# blackmagic_richardeoin.net
KiCad netlist of a schematic drawn in EAGLE
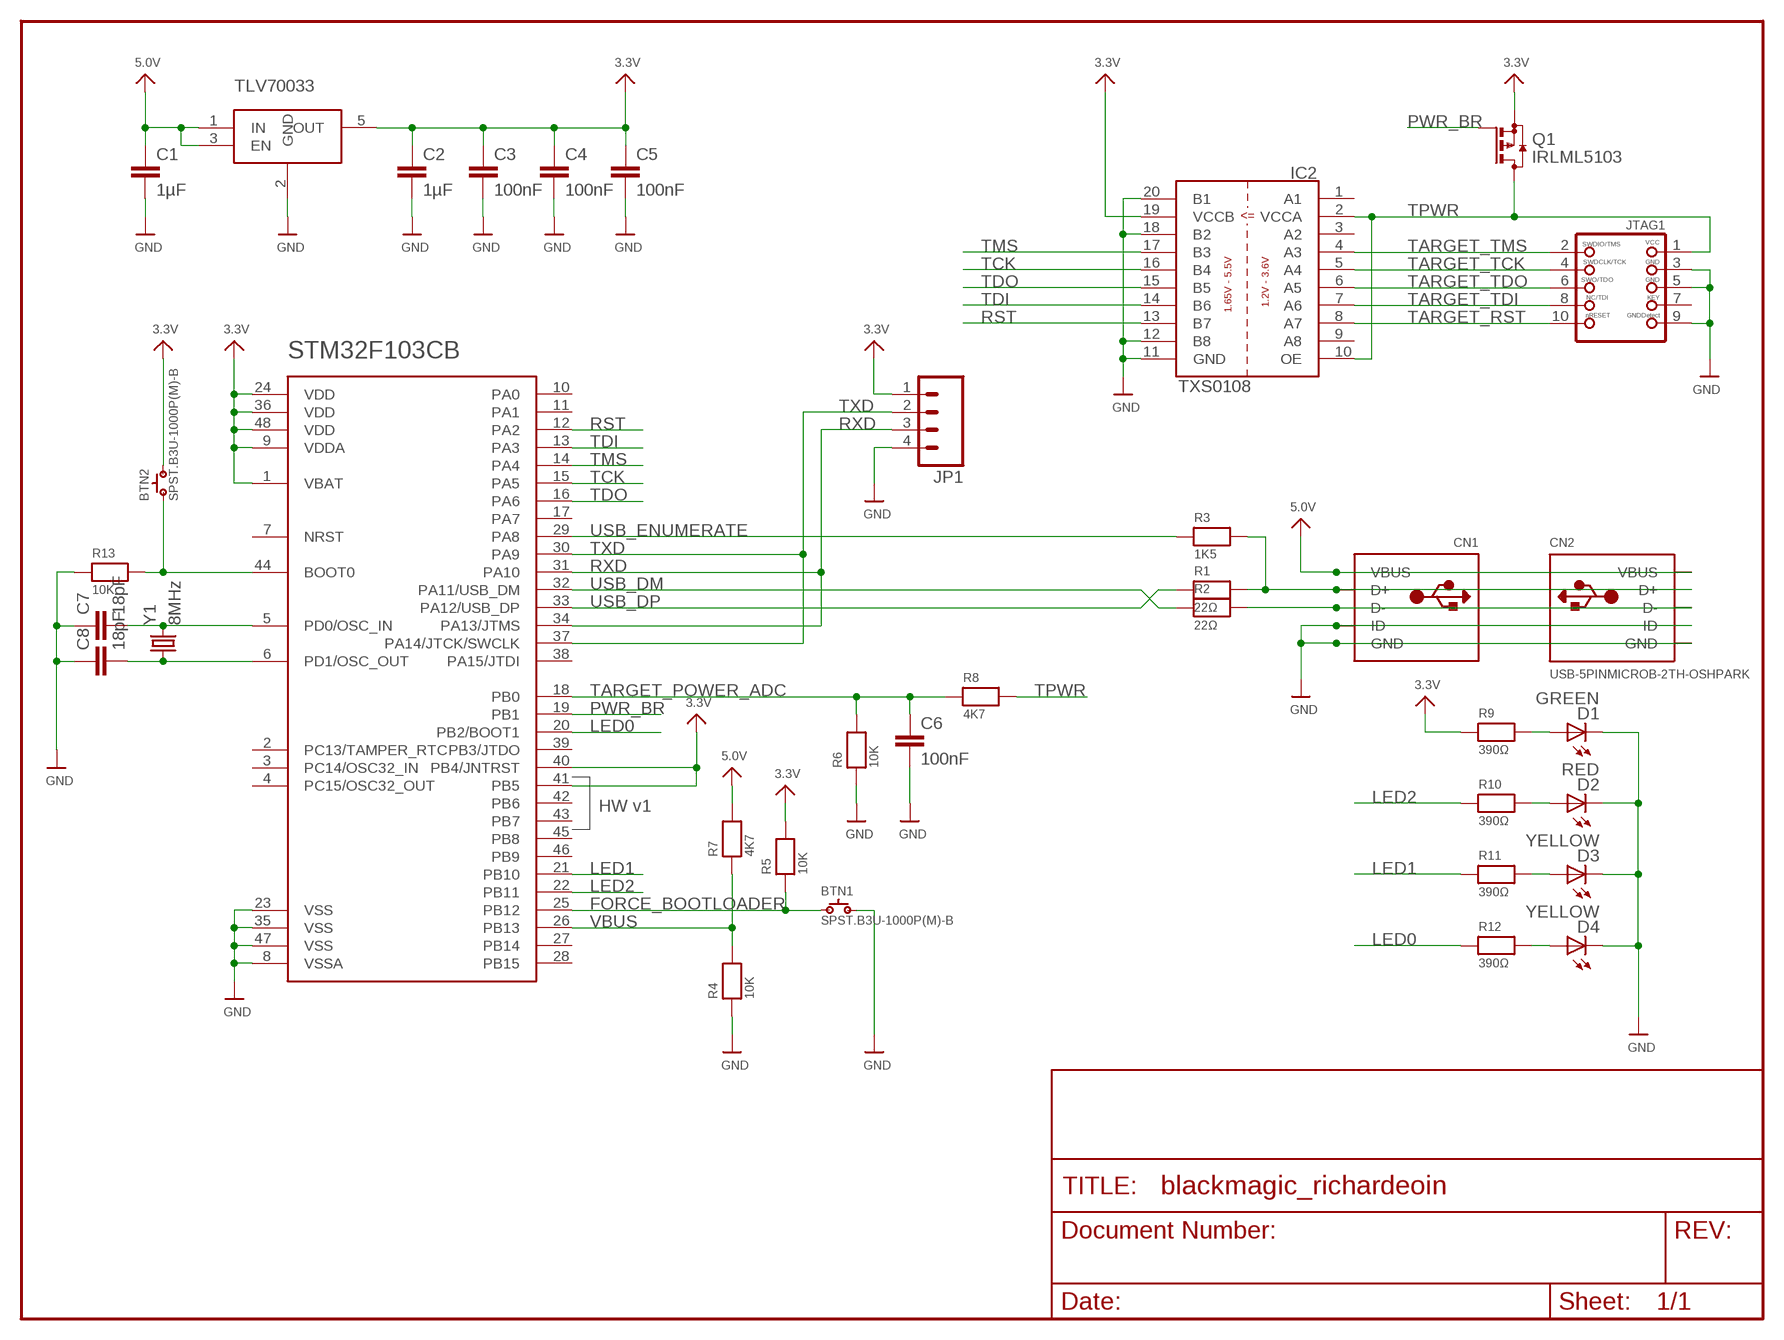
[diagram p0: schematic, sheet 1]

(export (version "E")
  (design (tool "Eeschema 10.0.6"))
  (components
    (comp (ref "BTN1")
      (value "SPST.B3U-1000P(M)-B")
      (footprint "eagle-import:B3U-1000P(M)-B")
      (libsource (lib "eagle-import") (part "SPST.B3U-1000P(M)-B"))
    )
    (comp (ref "BTN2")
      (value "SPST.B3U-1000P(M)-B")
      (footprint "eagle-import:B3U-1000P(M)-B")
      (libsource (lib "eagle-import") (part "SPST.B3U-1000P(M)-B"))
    )
    (comp (ref "C1")
      (value "1µF")
      (footprint "eagle-import:C0603K")
      (libsource (lib "eagle-import") (part "C-EUC0603K"))
    )
    (comp (ref "C2")
      (value "1µF")
      (footprint "eagle-import:C0603K")
      (libsource (lib "eagle-import") (part "C-EUC0603K"))
    )
    (comp (ref "C3")
      (value "100nF")
      (footprint "eagle-import:C0603K")
      (libsource (lib "eagle-import") (part "C-EUC0603K"))
    )
    (comp (ref "C4")
      (value "100nF")
      (footprint "eagle-import:C0603K")
      (libsource (lib "eagle-import") (part "C-EUC0603K"))
    )
    (comp (ref "C5")
      (value "100nF")
      (footprint "eagle-import:C0603K")
      (libsource (lib "eagle-import") (part "C-EUC0603K"))
    )
    (comp (ref "C6")
      (value "100nF")
      (footprint "eagle-import:C0603K")
      (libsource (lib "eagle-import") (part "C-EUC0603K"))
    )
    (comp (ref "C7")
      (value "18pF")
      (footprint "eagle-import:C0603K")
      (libsource (lib "eagle-import") (part "C-EUC0603K"))
    )
    (comp (ref "C8")
      (value "18pF")
      (footprint "eagle-import:C0603K")
      (libsource (lib "eagle-import") (part "C-EUC0603K"))
    )
    (comp (ref "CN1")
      (value "USBMINIB")
      (footprint "eagle-import:USB-MINIB")
      (libsource (lib "eagle-import") (part "USBMINIB"))
    )
    (comp (ref "CN2")
      (value "USB-5PINMICROB-2TH-OSHPARK")
      (footprint "eagle-import:USB-MICROB-2TH-OSHPARK")
      (libsource (lib "eagle-import") (part "USB-5PINMICROB-2TH-OSHPARK"))
    )
    (comp (ref "D1")
      (value "GREEN")
      (footprint "eagle-import:CHIPLED_0603")
      (libsource (lib "eagle-import") (part "LEDCHIPLED_0603"))
    )
    (comp (ref "D2")
      (value "RED")
      (footprint "eagle-import:CHIPLED_0603")
      (libsource (lib "eagle-import") (part "LEDCHIPLED_0603"))
    )
    (comp (ref "D3")
      (value "YELLOW")
      (footprint "eagle-import:CHIPLED_0603")
      (libsource (lib "eagle-import") (part "LEDCHIPLED_0603"))
    )
    (comp (ref "D4")
      (value "YELLOW")
      (footprint "eagle-import:CHIPLED_0603")
      (libsource (lib "eagle-import") (part "LEDCHIPLED_0603"))
    )
    (comp (ref "IC1")
      (value "STM32F_48PIN")
      (footprint "eagle-import:TQFP48")
      (libsource (lib "eagle-import") (part "STM32F_48PIN"))
    )
    (comp (ref "IC2")
      (value "TXS0108")
      (footprint "eagle-import:TSSOP20")
      (libsource (lib "eagle-import") (part "TX0108PWR"))
    )
    (comp (ref "IC3")
      (value "TLV70033DCK")
      (footprint "eagle-import:SC70-5L")
      (libsource (lib "eagle-import") (part "TLV700DCK"))
    )
    (comp (ref "JP1")
      (value "M04LOCK")
      (footprint "eagle-import:1X04_LOCK")
      (libsource (lib "eagle-import") (part "M04LOCK"))
    )
    (comp (ref "JTAG1")
      (value "JTAG-CORTEXM3TH")
      (footprint "eagle-import:2X05_1.27MM_TH")
      (libsource (lib "eagle-import") (part "JTAG-CORTEXM3TH"))
    )
    (comp (ref "Q1")
      (value "IRLML5103")
      (footprint "eagle-import:SOT23")
      (libsource (lib "eagle-import") (part "BSS84"))
    )
    (comp (ref "R1")
      (value "22Ω")
      (footprint "eagle-import:0603-MINI")
      (libsource (lib "eagle-import") (part "RESISTOR0603MINI"))
    )
    (comp (ref "R2")
      (value "22Ω")
      (footprint "eagle-import:0603-MINI")
      (libsource (lib "eagle-import") (part "RESISTOR0603MINI"))
    )
    (comp (ref "R3")
      (value "1K5")
      (footprint "eagle-import:0603-MINI")
      (libsource (lib "eagle-import") (part "RESISTOR0603MINI"))
    )
    (comp (ref "R4")
      (value "10K")
      (footprint "eagle-import:0603-MINI")
      (libsource (lib "eagle-import") (part "RESISTOR0603MINI"))
    )
    (comp (ref "R5")
      (value "10K")
      (footprint "eagle-import:0603-MINI")
      (libsource (lib "eagle-import") (part "RESISTOR0603MINI"))
    )
    (comp (ref "R6")
      (value "10K")
      (footprint "eagle-import:0603-MINI")
      (libsource (lib "eagle-import") (part "RESISTOR0603MINI"))
    )
    (comp (ref "R7")
      (value "4K7")
      (footprint "eagle-import:0603-MINI")
      (libsource (lib "eagle-import") (part "RESISTOR0603MINI"))
    )
    (comp (ref "R8")
      (value "4K7")
      (footprint "eagle-import:0603-MINI")
      (libsource (lib "eagle-import") (part "RESISTOR0603MINI"))
    )
    (comp (ref "R9")
      (value "390Ω")
      (footprint "eagle-import:0603-MINI")
      (libsource (lib "eagle-import") (part "RESISTOR0603MINI"))
    )
    (comp (ref "R10")
      (value "390Ω")
      (footprint "eagle-import:0603-MINI")
      (libsource (lib "eagle-import") (part "RESISTOR0603MINI"))
    )
    (comp (ref "R11")
      (value "390Ω")
      (footprint "eagle-import:0603-MINI")
      (libsource (lib "eagle-import") (part "RESISTOR0603MINI"))
    )
    (comp (ref "R12")
      (value "390Ω")
      (footprint "eagle-import:0603-MINI")
      (libsource (lib "eagle-import") (part "RESISTOR0603MINI"))
    )
    (comp (ref "R13")
      (value "10K")
      (footprint "eagle-import:0603-MINI")
      (libsource (lib "eagle-import") (part "RESISTOR0603MINI"))
    )
    (comp (ref "Y1")
      (value "8MHz")
      (footprint "eagle-import:CRYSTAL-SMD-5X3")
      (libsource (lib "eagle-import") (part "CRYSTAL5X3"))
    )
  )
  (nets
    (net (code "1") (name "/FORCE_BOOTLOADER") (class "Default")
      (node (ref "BTN1") (pin "1") (pinfunction "1_1") (pintype "bidirectional"))
      (node (ref "IC1") (pin "25") (pinfunction "PB12_25") (pintype "bidirectional"))
      (node (ref "R5") (pin "1") (pinfunction "1_1") (pintype "passive"))
    )
    (net (code "2") (name "/LED0") (class "Default")
      (node (ref "IC1") (pin "20") (pinfunction "PB2/BOOT1_20") (pintype "bidirectional"))
      (node (ref "R12") (pin "1") (pinfunction "1_1") (pintype "passive"))
    )
    (net (code "3") (name "/LED1") (class "Default")
      (node (ref "IC1") (pin "21") (pinfunction "PB10_21") (pintype "bidirectional"))
      (node (ref "R11") (pin "1") (pinfunction "1_1") (pintype "passive"))
    )
    (net (code "4") (name "/LED2") (class "Default")
      (node (ref "IC1") (pin "22") (pinfunction "PB11_22") (pintype "bidirectional"))
      (node (ref "R10") (pin "1") (pinfunction "1_1") (pintype "passive"))
    )
    (net (code "5") (name "/PWR_BR") (class "Default")
      (node (ref "IC1") (pin "19") (pinfunction "PB1_19") (pintype "bidirectional"))
      (node (ref "Q1") (pin "1") (pinfunction "G_1") (pintype "passive"))
    )
    (net (code "6") (name "/RST") (class "Default")
      (node (ref "IC1") (pin "12") (pinfunction "PA2_12") (pintype "bidirectional"))
      (node (ref "IC2") (pin "13") (pinfunction "B7_13") (pintype "bidirectional"))
    )
    (net (code "7") (name "/RXD") (class "Default")
      (node (ref "IC1") (pin "31") (pinfunction "PA10_31") (pintype "bidirectional"))
      (node (ref "IC1") (pin "34") (pinfunction "PA13/JTMS_34") (pintype "bidirectional"))
      (node (ref "JP1") (pin "3") (pinfunction "3_3") (pintype "passive"))
    )
    (net (code "8") (name "/TARGET_POWER_ADC") (class "Default")
      (node (ref "C6") (pin "1") (pinfunction "1_1") (pintype "passive"))
      (node (ref "IC1") (pin "18") (pinfunction "PB0_18") (pintype "bidirectional"))
      (node (ref "R6") (pin "2") (pinfunction "2_2") (pintype "passive"))
      (node (ref "R8") (pin "1") (pinfunction "1_1") (pintype "passive"))
    )
    (net (code "9") (name "/TARGET_RST") (class "Default")
      (node (ref "IC2") (pin "8") (pinfunction "A7_8") (pintype "bidirectional"))
      (node (ref "JTAG1") (pin "10") (pinfunction "10_10") (pintype "passive"))
    )
    (net (code "10") (name "/TARGET_TCK") (class "Default")
      (node (ref "IC2") (pin "5") (pinfunction "A4_5") (pintype "bidirectional"))
      (node (ref "JTAG1") (pin "4") (pinfunction "4_4") (pintype "passive"))
    )
    (net (code "11") (name "/TARGET_TDI") (class "Default")
      (node (ref "IC2") (pin "7") (pinfunction "A6_7") (pintype "bidirectional"))
      (node (ref "JTAG1") (pin "8") (pinfunction "8_8") (pintype "passive"))
    )
    (net (code "12") (name "/TARGET_TDO") (class "Default")
      (node (ref "IC2") (pin "6") (pinfunction "A5_6") (pintype "bidirectional"))
      (node (ref "JTAG1") (pin "6") (pinfunction "6_6") (pintype "passive"))
    )
    (net (code "13") (name "/TARGET_TMS") (class "Default")
      (node (ref "IC2") (pin "4") (pinfunction "A3_4") (pintype "bidirectional"))
      (node (ref "JTAG1") (pin "2") (pinfunction "2_2") (pintype "passive"))
    )
    (net (code "14") (name "/TCK") (class "Default")
      (node (ref "IC1") (pin "15") (pinfunction "PA5_15") (pintype "bidirectional"))
      (node (ref "IC2") (pin "16") (pinfunction "B4_16") (pintype "bidirectional"))
    )
    (net (code "15") (name "/TDI") (class "Default")
      (node (ref "IC1") (pin "13") (pinfunction "PA3_13") (pintype "bidirectional"))
      (node (ref "IC2") (pin "14") (pinfunction "B6_14") (pintype "bidirectional"))
    )
    (net (code "16") (name "/TDO") (class "Default")
      (node (ref "IC1") (pin "16") (pinfunction "PA6_16") (pintype "bidirectional"))
      (node (ref "IC2") (pin "15") (pinfunction "B5_15") (pintype "bidirectional"))
    )
    (net (code "17") (name "/TMS") (class "Default")
      (node (ref "IC1") (pin "14") (pinfunction "PA4_14") (pintype "bidirectional"))
      (node (ref "IC2") (pin "17") (pinfunction "B3_17") (pintype "bidirectional"))
    )
    (net (code "18") (name "/TPWR") (class "Default")
      (node (ref "IC2") (pin "10") (pinfunction "OE_10") (pintype "input"))
      (node (ref "IC2") (pin "2") (pinfunction "VCCA_2") (pintype "passive"))
      (node (ref "JTAG1") (pin "1") (pinfunction "1_1") (pintype "passive"))
      (node (ref "Q1") (pin "3") (pinfunction "D_3") (pintype "passive"))
      (node (ref "R8") (pin "2") (pinfunction "2_2") (pintype "passive"))
    )
    (net (code "19") (name "/TXD") (class "Default")
      (node (ref "IC1") (pin "30") (pinfunction "PA9_30") (pintype "bidirectional"))
      (node (ref "IC1") (pin "37") (pinfunction "PA14/JTCK/SWCLK_37") (pintype "bidirectional"))
      (node (ref "JP1") (pin "2") (pinfunction "2_2") (pintype "passive"))
    )
    (net (code "20") (name "/USB_DM") (class "Default")
      (node (ref "IC1") (pin "32") (pinfunction "PA11/USB_DM_32") (pintype "bidirectional"))
      (node (ref "R2") (pin "1") (pinfunction "1_1") (pintype "passive"))
    )
    (net (code "21") (name "/USB_DP") (class "Default")
      (node (ref "IC1") (pin "33") (pinfunction "PA12/USB_DP_33") (pintype "bidirectional"))
      (node (ref "R1") (pin "1") (pinfunction "1_1") (pintype "passive"))
    )
    (net (code "22") (name "/USB_ENUMERATE") (class "Default")
      (node (ref "IC1") (pin "29") (pinfunction "PA8_29") (pintype "bidirectional"))
      (node (ref "R3") (pin "1") (pinfunction "1_1") (pintype "passive"))
    )
    (net (code "23") (name "/VBUS") (class "Default")
      (node (ref "IC1") (pin "26") (pinfunction "PB13_26") (pintype "bidirectional"))
      (node (ref "R4") (pin "2") (pinfunction "2_2") (pintype "passive"))
      (node (ref "R7") (pin "1") (pinfunction "1_1") (pintype "passive"))
    )
    (net (code "24") (name "3.3V") (class "Default")
      (node (ref "BTN2") (pin "2") (pinfunction "2_2") (pintype "bidirectional"))
      (node (ref "C2") (pin "1") (pinfunction "1_1") (pintype "passive"))
      (node (ref "C3") (pin "1") (pinfunction "1_1") (pintype "passive"))
      (node (ref "C4") (pin "1") (pinfunction "1_1") (pintype "passive"))
      (node (ref "C5") (pin "1") (pinfunction "1_1") (pintype "passive"))
      (node (ref "IC1") (pin "1") (pinfunction "VBAT_1") (pintype "bidirectional"))
      (node (ref "IC1") (pin "24") (pinfunction "VDD_24") (pintype "bidirectional"))
      (node (ref "IC1") (pin "36") (pinfunction "VDD_36") (pintype "bidirectional"))
      (node (ref "IC1") (pin "40") (pinfunction "PB4/JNTRST_40") (pintype "bidirectional"))
      (node (ref "IC1") (pin "41") (pinfunction "PB5_41") (pintype "bidirectional"))
      (node (ref "IC1") (pin "48") (pinfunction "VDD_48") (pintype "bidirectional"))
      (node (ref "IC1") (pin "9") (pinfunction "VDDA_9") (pintype "bidirectional"))
      (node (ref "IC2") (pin "19") (pinfunction "VCCB_19") (pintype "passive"))
      (node (ref "IC3") (pin "5") (pinfunction "OUT_5") (pintype "bidirectional"))
      (node (ref "JP1") (pin "1") (pinfunction "1_1") (pintype "passive"))
      (node (ref "Q1") (pin "2") (pinfunction "S_2") (pintype "passive"))
      (node (ref "R5") (pin "2") (pinfunction "2_2") (pintype "passive"))
      (node (ref "R9") (pin "1") (pinfunction "1_1") (pintype "passive"))
    )
    (net (code "25") (name "5.0V") (class "Default")
      (node (ref "C1") (pin "1") (pinfunction "1_1") (pintype "passive"))
      (node (ref "CN1") (pin "VBUS") (pinfunction "VBUS_VBUS") (pintype "power_in"))
      (node (ref "CN2") (pin "VBUS") (pinfunction "VBUS_VBUS") (pintype "power_in"))
      (node (ref "IC3") (pin "1") (pinfunction "IN_1") (pintype "bidirectional"))
      (node (ref "IC3") (pin "3") (pinfunction "EN_3") (pintype "bidirectional"))
      (node (ref "R7") (pin "2") (pinfunction "2_2") (pintype "passive"))
    )
    (net (code "26") (name "GND") (class "Default")
      (node (ref "BTN1") (pin "2") (pinfunction "2_2") (pintype "bidirectional"))
      (node (ref "C1") (pin "2") (pinfunction "2_2") (pintype "passive"))
      (node (ref "C2") (pin "2") (pinfunction "2_2") (pintype "passive"))
      (node (ref "C3") (pin "2") (pinfunction "2_2") (pintype "passive"))
      (node (ref "C4") (pin "2") (pinfunction "2_2") (pintype "passive"))
      (node (ref "C5") (pin "2") (pinfunction "2_2") (pintype "passive"))
      (node (ref "C6") (pin "2") (pinfunction "2_2") (pintype "passive"))
      (node (ref "C7") (pin "1") (pinfunction "1_1") (pintype "passive"))
      (node (ref "C8") (pin "1") (pinfunction "1_1") (pintype "passive"))
      (node (ref "CN1") (pin "GND") (pinfunction "GND_GND") (pintype "power_in"))
      (node (ref "CN1") (pin "ID") (pinfunction "ID_ID") (pintype "bidirectional"))
      (node (ref "CN2") (pin "GND") (pinfunction "GND_GND") (pintype "power_in"))
      (node (ref "CN2") (pin "ID") (pinfunction "ID_ID") (pintype "bidirectional"))
      (node (ref "D1") (pin "C") (pinfunction "C_C") (pintype "passive"))
      (node (ref "D2") (pin "C") (pinfunction "C_C") (pintype "passive"))
      (node (ref "D3") (pin "C") (pinfunction "C_C") (pintype "passive"))
      (node (ref "D4") (pin "C") (pinfunction "C_C") (pintype "passive"))
      (node (ref "IC1") (pin "23") (pinfunction "VSS_23") (pintype "bidirectional"))
      (node (ref "IC1") (pin "35") (pinfunction "VSS_35") (pintype "bidirectional"))
      (node (ref "IC1") (pin "47") (pinfunction "VSS_47") (pintype "bidirectional"))
      (node (ref "IC1") (pin "8") (pinfunction "VSSA_8") (pintype "bidirectional"))
      (node (ref "IC2") (pin "11") (pinfunction "GND_11") (pintype "passive"))
      (node (ref "IC2") (pin "12") (pinfunction "B8_12") (pintype "bidirectional"))
      (node (ref "IC2") (pin "18") (pinfunction "B2_18") (pintype "bidirectional"))
      (node (ref "IC2") (pin "20") (pinfunction "B1_20") (pintype "bidirectional"))
      (node (ref "IC3") (pin "2") (pinfunction "GND_2") (pintype "bidirectional"))
      (node (ref "JP1") (pin "4") (pinfunction "4_4") (pintype "passive"))
      (node (ref "JTAG1") (pin "3") (pinfunction "3_3") (pintype "passive"))
      (node (ref "JTAG1") (pin "5") (pinfunction "5_5") (pintype "passive"))
      (node (ref "JTAG1") (pin "9") (pinfunction "9_9") (pintype "passive"))
      (node (ref "R13") (pin "1") (pinfunction "1_1") (pintype "passive"))
      (node (ref "R4") (pin "1") (pinfunction "1_1") (pintype "passive"))
      (node (ref "R6") (pin "1") (pinfunction "1_1") (pintype "passive"))
    )
    (net (code "27") (name "Net-(CN1-PadD+)") (class "Default")
      (node (ref "CN1") (pin "D+") (pinfunction "D+_D+") (pintype "bidirectional"))
      (node (ref "CN2") (pin "D+") (pinfunction "D+_D+") (pintype "bidirectional"))
      (node (ref "R1") (pin "2") (pinfunction "2_2") (pintype "passive"))
      (node (ref "R3") (pin "2") (pinfunction "2_2") (pintype "passive"))
    )
    (net (code "28") (name "Net-(CN1-PadD-)") (class "Default")
      (node (ref "CN1") (pin "D-") (pinfunction "D-_D-") (pintype "bidirectional"))
      (node (ref "CN2") (pin "D-") (pinfunction "D-_D-") (pintype "bidirectional"))
      (node (ref "R2") (pin "2") (pinfunction "2_2") (pintype "passive"))
    )
    (net (code "29") (name "Net-(D1-PadA)") (class "Default")
      (node (ref "D1") (pin "A") (pinfunction "A_A") (pintype "passive"))
      (node (ref "R9") (pin "2") (pinfunction "2_2") (pintype "passive"))
    )
    (net (code "30") (name "Net-(D2-PadA)") (class "Default")
      (node (ref "D2") (pin "A") (pinfunction "A_A") (pintype "passive"))
      (node (ref "R10") (pin "2") (pinfunction "2_2") (pintype "passive"))
    )
    (net (code "31") (name "Net-(D3-PadA)") (class "Default")
      (node (ref "D3") (pin "A") (pinfunction "A_A") (pintype "passive"))
      (node (ref "R11") (pin "2") (pinfunction "2_2") (pintype "passive"))
    )
    (net (code "32") (name "Net-(D4-PadA)") (class "Default")
      (node (ref "D4") (pin "A") (pinfunction "A_A") (pintype "passive"))
      (node (ref "R12") (pin "2") (pinfunction "2_2") (pintype "passive"))
    )
    (net (code "33") (name "Net-(IC1-BOOT0)") (class "Default")
      (node (ref "BTN2") (pin "1") (pinfunction "1_1") (pintype "bidirectional"))
      (node (ref "IC1") (pin "44") (pinfunction "BOOT0_44") (pintype "bidirectional"))
      (node (ref "R13") (pin "2") (pinfunction "2_2") (pintype "passive"))
    )
    (net (code "34") (name "Net-(IC1-PD0{slash}OSC_IN)") (class "Default")
      (node (ref "C7") (pin "2") (pinfunction "2_2") (pintype "passive"))
      (node (ref "IC1") (pin "5") (pinfunction "PD0/OSC_IN_5") (pintype "bidirectional"))
      (node (ref "Y1") (pin "3") (pinfunction "2_3") (pintype "passive"))
    )
    (net (code "35") (name "Net-(IC1-PD1{slash}OSC_OUT)") (class "Default")
      (node (ref "C8") (pin "2") (pinfunction "2_2") (pintype "passive"))
      (node (ref "IC1") (pin "6") (pinfunction "PD1/OSC_OUT_6") (pintype "bidirectional"))
      (node (ref "Y1") (pin "1") (pinfunction "1_1") (pintype "passive"))
    )
    (net (code "36") (name "unconnected-(IC1-NRST-Pad7)") (class "Default")
      (node (ref "IC1") (pin "7") (pinfunction "NRST_7") (pintype "bidirectional"))
    )
    (net (code "37") (name "unconnected-(IC1-PA0-Pad10)") (class "Default")
      (node (ref "IC1") (pin "10") (pinfunction "PA0_10") (pintype "bidirectional"))
    )
    (net (code "38") (name "unconnected-(IC1-PA1-Pad11)") (class "Default")
      (node (ref "IC1") (pin "11") (pinfunction "PA1_11") (pintype "bidirectional"))
    )
    (net (code "39") (name "unconnected-(IC1-PA7-Pad17)") (class "Default")
      (node (ref "IC1") (pin "17") (pinfunction "PA7_17") (pintype "bidirectional"))
    )
    (net (code "40") (name "unconnected-(IC1-PA15{slash}JTDI-Pad38)") (class "Default")
      (node (ref "IC1") (pin "38") (pinfunction "PA15/JTDI_38") (pintype "bidirectional"))
    )
    (net (code "41") (name "unconnected-(IC1-PB3{slash}JTDO-Pad39)") (class "Default")
      (node (ref "IC1") (pin "39") (pinfunction "PB3/JTDO_39") (pintype "bidirectional"))
    )
    (net (code "42") (name "unconnected-(IC1-PB6-Pad42)") (class "Default")
      (node (ref "IC1") (pin "42") (pinfunction "PB6_42") (pintype "bidirectional"))
    )
    (net (code "43") (name "unconnected-(IC1-PB7-Pad43)") (class "Default")
      (node (ref "IC1") (pin "43") (pinfunction "PB7_43") (pintype "bidirectional"))
    )
    (net (code "44") (name "unconnected-(IC1-PB8-Pad45)") (class "Default")
      (node (ref "IC1") (pin "45") (pinfunction "PB8_45") (pintype "bidirectional"))
    )
    (net (code "45") (name "unconnected-(IC1-PB9-Pad46)") (class "Default")
      (node (ref "IC1") (pin "46") (pinfunction "PB9_46") (pintype "bidirectional"))
    )
    (net (code "46") (name "unconnected-(IC1-PB14-Pad27)") (class "Default")
      (node (ref "IC1") (pin "27") (pinfunction "PB14_27") (pintype "bidirectional"))
    )
    (net (code "47") (name "unconnected-(IC1-PB15-Pad28)") (class "Default")
      (node (ref "IC1") (pin "28") (pinfunction "PB15_28") (pintype "bidirectional"))
    )
    (net (code "48") (name "unconnected-(IC1-PC13{slash}TAMPER_RTC-Pad2)") (class "Default")
      (node (ref "IC1") (pin "2") (pinfunction "PC13/TAMPER_RTC_2") (pintype "bidirectional"))
    )
    (net (code "49") (name "unconnected-(IC1-PC14{slash}OSC32_IN-Pad3)") (class "Default")
      (node (ref "IC1") (pin "3") (pinfunction "PC14/OSC32_IN_3") (pintype "bidirectional"))
    )
    (net (code "50") (name "unconnected-(IC1-PC15{slash}OSC32_OUT-Pad4)") (class "Default")
      (node (ref "IC1") (pin "4") (pinfunction "PC15/OSC32_OUT_4") (pintype "bidirectional"))
    )
    (net (code "51") (name "unconnected-(IC2-A1-Pad1)") (class "Default")
      (node (ref "IC2") (pin "1") (pinfunction "A1_1") (pintype "bidirectional"))
    )
    (net (code "52") (name "unconnected-(IC2-A2-Pad3)") (class "Default")
      (node (ref "IC2") (pin "3") (pinfunction "A2_3") (pintype "bidirectional"))
    )
    (net (code "53") (name "unconnected-(IC2-A8-Pad9)") (class "Default")
      (node (ref "IC2") (pin "9") (pinfunction "A8_9") (pintype "bidirectional"))
    )
    (net (code "54") (name "unconnected-(JTAG1-Pad7)") (class "Default")
      (node (ref "JTAG1") (pin "7") (pinfunction "7_7") (pintype "passive"))
    )
  )
)
